# Control_Unit.net
KiCad netlist of a schematic drawn in EAGLE
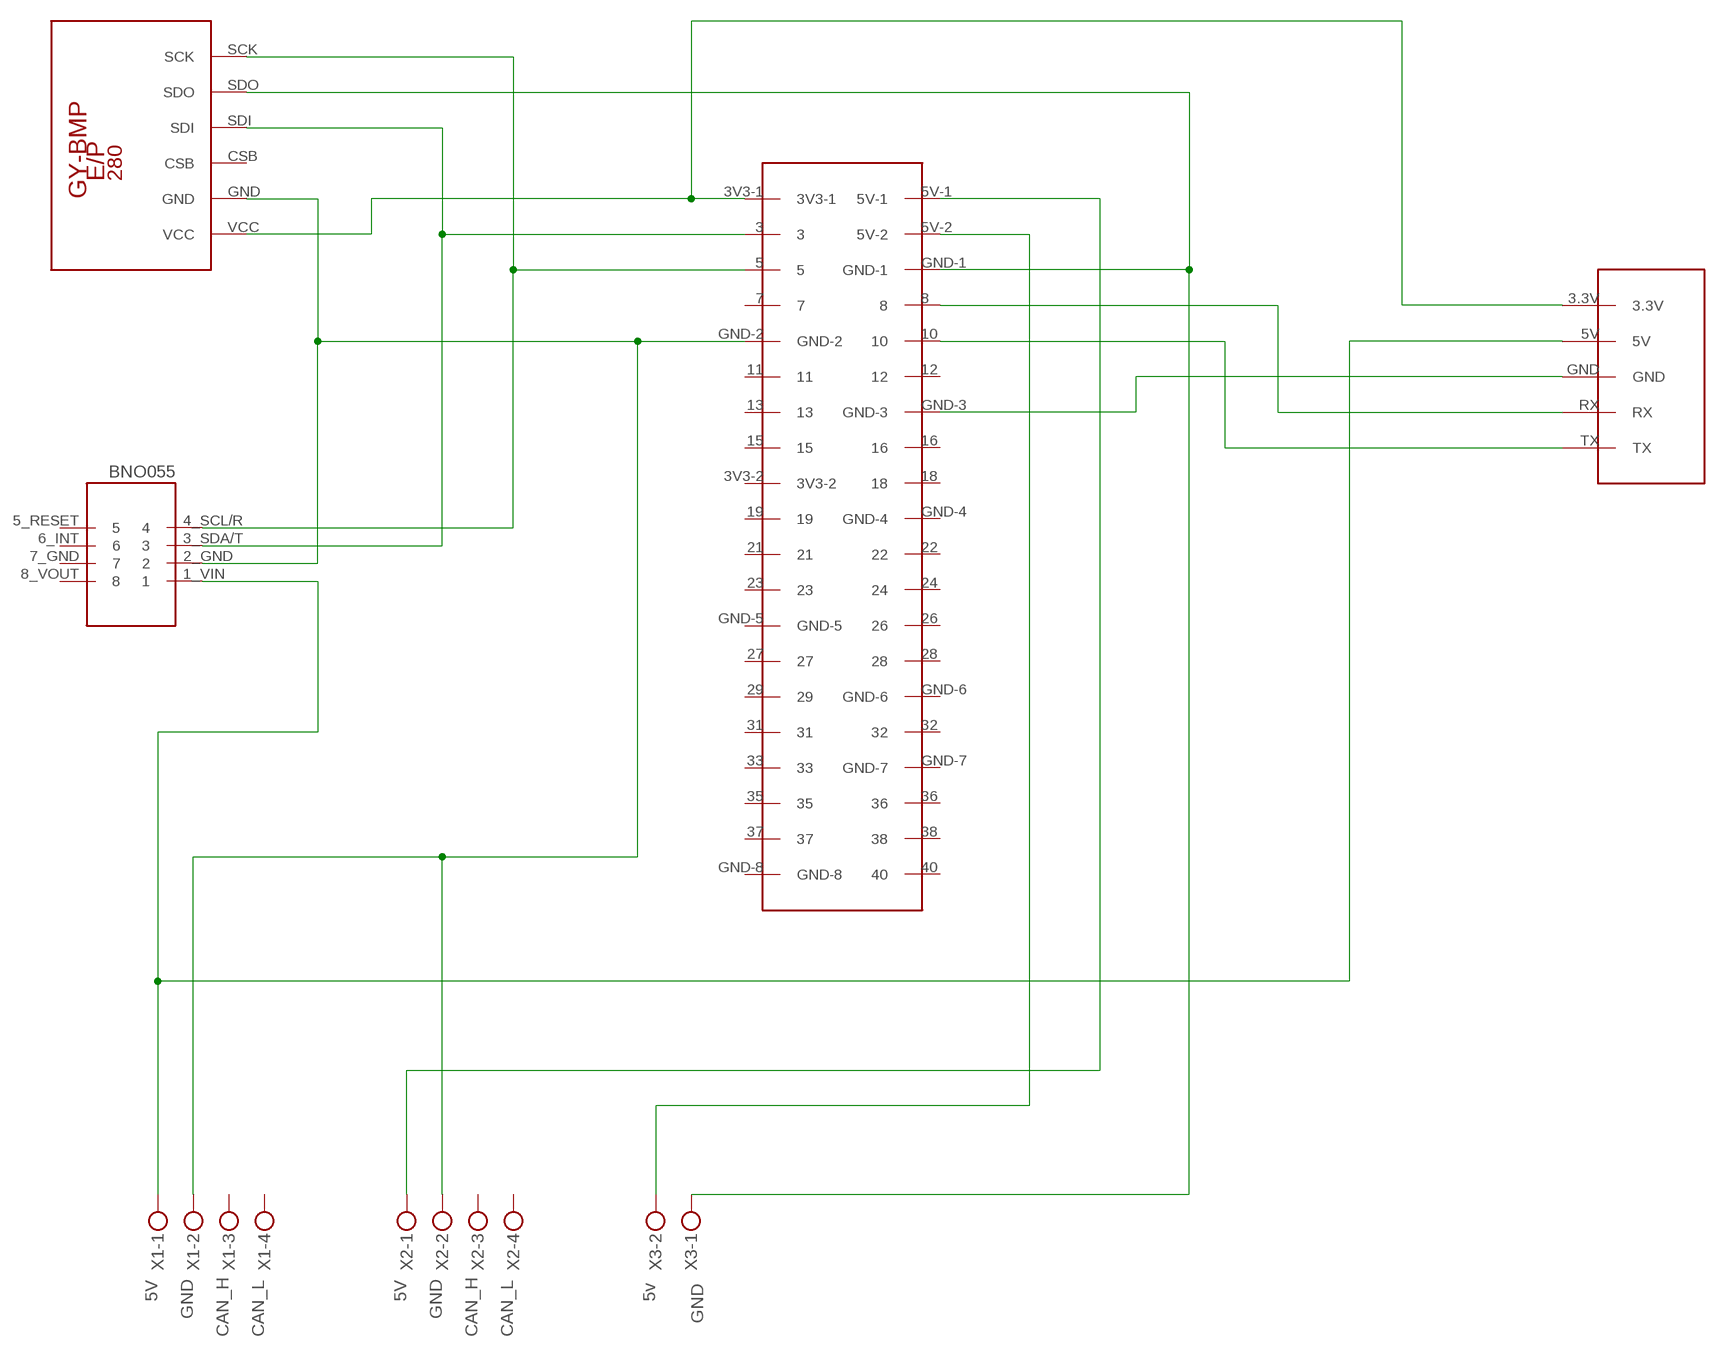
[diagram p0: schematic, sheet 1]

(export (version "E")
  (design (tool "Eeschema 10.0.6"))
  (components
    (comp (ref "JN1")
      (value "JETSON_NANO")
      (footprint "eagle-import:JETSON_NANO")
      (libsource (lib "eagle-import") (part "JETSON_NANO"))
    )
    (comp (ref "U$1")
      (value "GY-BPM280")
      (footprint "eagle-import:GY-BMP280-FOOTPRINT")
      (libsource (lib "eagle-import") (part "GY-BPM280"))
    )
    (comp (ref "U$2")
      (value "BNO055")
      (footprint "eagle-import:BNO055")
      (libsource (lib "eagle-import") (part "BNO055"))
    )
    (comp (ref "U$3")
      (value "WIRELESS_PINS")
      (footprint "eagle-import:WIRELESS_PINS")
      (libsource (lib "eagle-import") (part "WIRELESS_PINS"))
    )
    (comp (ref "X1")
      (value "MKDSN1,5/4-5,08")
      (footprint "eagle-import:MKDSN1,5_4-5,08")
      (libsource (lib "eagle-import") (part "MKDSN1,5/4-5,08"))
    )
    (comp (ref "X2")
      (value "MKDSN1,5/4-5,08")
      (footprint "eagle-import:MKDSN1,5_4-5,08")
      (libsource (lib "eagle-import") (part "MKDSN1,5/4-5,08"))
    )
    (comp (ref "X3")
      (value "MKDSN1,5/2-5,08")
      (footprint "eagle-import:MKDSN1,5_2-5,08")
      (libsource (lib "eagle-import") (part "MKDSN1,5/2-5,08"))
    )
  )
  (nets
    (net (code "1") (name "Net-(JN1-Pad3V3-1)") (class "Default")
      (node (ref "JN1") (pin "3V3-1") (pinfunction "3V3-1_3V3-1") (pintype "bidirectional"))
      (node (ref "U$1") (pin "VCC") (pinfunction "VCC_VCC") (pintype "bidirectional"))
      (node (ref "U$3") (pin "3.3V") (pinfunction "3.3V_3.3V") (pintype "bidirectional"))
    )
    (net (code "2") (name "Net-(JN1-Pad8)") (class "Default")
      (node (ref "JN1") (pin "8") (pinfunction "8_8") (pintype "bidirectional"))
      (node (ref "U$3") (pin "RX") (pinfunction "RX_RX") (pintype "bidirectional"))
    )
    (net (code "3") (name "Net-(JN1-Pad10)") (class "Default")
      (node (ref "JN1") (pin "10") (pinfunction "10_10") (pintype "bidirectional"))
      (node (ref "U$3") (pin "TX") (pinfunction "TX_TX") (pintype "bidirectional"))
    )
    (net (code "4") (name "Net-(JN1-PadGND-3)") (class "Default")
      (node (ref "JN1") (pin "GND-3") (pinfunction "GND-3_GND-3") (pintype "bidirectional"))
      (node (ref "U$3") (pin "GND") (pinfunction "GND_GND") (pintype "bidirectional"))
    )
    (net (code "5") (name "Net-(U$2-1)") (class "Default")
      (node (ref "U$2") (pin "1_VIN") (pinfunction "1_1_VIN") (pintype "bidirectional"))
      (node (ref "U$3") (pin "5V") (pinfunction "5V_5V") (pintype "bidirectional"))
      (node (ref "X1") (pin "1") (pinfunction "KL_1") (pintype "passive"))
    )
    (net (code "6") (name "Net-(U$2-2)") (class "Default")
      (node (ref "JN1") (pin "GND-2") (pinfunction "GND-2_GND-2") (pintype "bidirectional"))
      (node (ref "U$1") (pin "GND") (pinfunction "GND_GND") (pintype "bidirectional"))
      (node (ref "U$2") (pin "2_GND") (pinfunction "2_2_GND") (pintype "bidirectional"))
      (node (ref "X1") (pin "2") (pinfunction "KL_2") (pintype "passive"))
      (node (ref "X2") (pin "2") (pinfunction "KL_2") (pintype "passive"))
    )
    (net (code "7") (name "Net-(U$2-3)") (class "Default")
      (node (ref "JN1") (pin "3") (pinfunction "3_3") (pintype "bidirectional"))
      (node (ref "U$1") (pin "SDI") (pinfunction "SDI_SDI") (pintype "bidirectional"))
      (node (ref "U$2") (pin "3_SDA/T") (pinfunction "3_3_SDA/T") (pintype "bidirectional"))
    )
    (net (code "8") (name "Net-(U$2-4)") (class "Default")
      (node (ref "JN1") (pin "5") (pinfunction "5_5") (pintype "bidirectional"))
      (node (ref "U$1") (pin "SCK") (pinfunction "SCK_SCK") (pintype "bidirectional"))
      (node (ref "U$2") (pin "4_SCL/R") (pinfunction "4_4_SCL/R") (pintype "bidirectional"))
    )
    (net (code "9") (name "Net-(X2A-KL)") (class "Default")
      (node (ref "JN1") (pin "5V-1") (pinfunction "5V-1_5V-1") (pintype "bidirectional"))
      (node (ref "X2") (pin "1") (pinfunction "KL_1") (pintype "passive"))
    )
    (net (code "10") (name "Net-(X3A-KL)") (class "Default")
      (node (ref "JN1") (pin "GND-1") (pinfunction "GND-1_GND-1") (pintype "bidirectional"))
      (node (ref "U$1") (pin "SDO") (pinfunction "SDO_SDO") (pintype "bidirectional"))
      (node (ref "X3") (pin "1") (pinfunction "KL_1") (pintype "passive"))
    )
    (net (code "11") (name "Net-(X3B-KL)") (class "Default")
      (node (ref "JN1") (pin "5V-2") (pinfunction "5V-2_5V-2") (pintype "bidirectional"))
      (node (ref "X3") (pin "2") (pinfunction "KL_2") (pintype "passive"))
    )
    (net (code "12") (name "unconnected-(JN1-Pad3V3-2)") (class "Default")
      (node (ref "JN1") (pin "3V3-2") (pinfunction "3V3-2_3V3-2") (pintype "bidirectional"))
    )
    (net (code "13") (name "unconnected-(JN1-Pad7)") (class "Default")
      (node (ref "JN1") (pin "7") (pinfunction "7_7") (pintype "bidirectional"))
    )
    (net (code "14") (name "unconnected-(JN1-Pad11)") (class "Default")
      (node (ref "JN1") (pin "11") (pinfunction "11_11") (pintype "bidirectional"))
    )
    (net (code "15") (name "unconnected-(JN1-Pad12)") (class "Default")
      (node (ref "JN1") (pin "12") (pinfunction "12_12") (pintype "bidirectional"))
    )
    (net (code "16") (name "unconnected-(JN1-Pad13)") (class "Default")
      (node (ref "JN1") (pin "13") (pinfunction "13_13") (pintype "bidirectional"))
    )
    (net (code "17") (name "unconnected-(JN1-Pad15)") (class "Default")
      (node (ref "JN1") (pin "15") (pinfunction "15_15") (pintype "bidirectional"))
    )
    (net (code "18") (name "unconnected-(JN1-Pad16)") (class "Default")
      (node (ref "JN1") (pin "16") (pinfunction "16_16") (pintype "bidirectional"))
    )
    (net (code "19") (name "unconnected-(JN1-Pad18)") (class "Default")
      (node (ref "JN1") (pin "18") (pinfunction "18_18") (pintype "bidirectional"))
    )
    (net (code "20") (name "unconnected-(JN1-Pad19)") (class "Default")
      (node (ref "JN1") (pin "19") (pinfunction "19_19") (pintype "bidirectional"))
    )
    (net (code "21") (name "unconnected-(JN1-Pad21)") (class "Default")
      (node (ref "JN1") (pin "21") (pinfunction "21_21") (pintype "bidirectional"))
    )
    (net (code "22") (name "unconnected-(JN1-Pad22)") (class "Default")
      (node (ref "JN1") (pin "22") (pinfunction "22_22") (pintype "bidirectional"))
    )
    (net (code "23") (name "unconnected-(JN1-Pad23)") (class "Default")
      (node (ref "JN1") (pin "23") (pinfunction "23_23") (pintype "bidirectional"))
    )
    (net (code "24") (name "unconnected-(JN1-Pad24)") (class "Default")
      (node (ref "JN1") (pin "24") (pinfunction "24_24") (pintype "bidirectional"))
    )
    (net (code "25") (name "unconnected-(JN1-Pad26)") (class "Default")
      (node (ref "JN1") (pin "26") (pinfunction "26_26") (pintype "bidirectional"))
    )
    (net (code "26") (name "unconnected-(JN1-Pad27)") (class "Default")
      (node (ref "JN1") (pin "27") (pinfunction "27_27") (pintype "bidirectional"))
    )
    (net (code "27") (name "unconnected-(JN1-Pad28)") (class "Default")
      (node (ref "JN1") (pin "28") (pinfunction "28_28") (pintype "bidirectional"))
    )
    (net (code "28") (name "unconnected-(JN1-Pad29)") (class "Default")
      (node (ref "JN1") (pin "29") (pinfunction "29_29") (pintype "bidirectional"))
    )
    (net (code "29") (name "unconnected-(JN1-Pad31)") (class "Default")
      (node (ref "JN1") (pin "31") (pinfunction "31_31") (pintype "bidirectional"))
    )
    (net (code "30") (name "unconnected-(JN1-Pad32)") (class "Default")
      (node (ref "JN1") (pin "32") (pinfunction "32_32") (pintype "bidirectional"))
    )
    (net (code "31") (name "unconnected-(JN1-Pad33)") (class "Default")
      (node (ref "JN1") (pin "33") (pinfunction "33_33") (pintype "bidirectional"))
    )
    (net (code "32") (name "unconnected-(JN1-Pad35)") (class "Default")
      (node (ref "JN1") (pin "35") (pinfunction "35_35") (pintype "bidirectional"))
    )
    (net (code "33") (name "unconnected-(JN1-Pad36)") (class "Default")
      (node (ref "JN1") (pin "36") (pinfunction "36_36") (pintype "bidirectional"))
    )
    (net (code "34") (name "unconnected-(JN1-Pad37)") (class "Default")
      (node (ref "JN1") (pin "37") (pinfunction "37_37") (pintype "bidirectional"))
    )
    (net (code "35") (name "unconnected-(JN1-Pad38)") (class "Default")
      (node (ref "JN1") (pin "38") (pinfunction "38_38") (pintype "bidirectional"))
    )
    (net (code "36") (name "unconnected-(JN1-Pad40)") (class "Default")
      (node (ref "JN1") (pin "40") (pinfunction "40_40") (pintype "bidirectional"))
    )
    (net (code "37") (name "unconnected-(JN1-PadGND-4)") (class "Default")
      (node (ref "JN1") (pin "GND-4") (pinfunction "GND-4_GND-4") (pintype "bidirectional"))
    )
    (net (code "38") (name "unconnected-(JN1-PadGND-5)") (class "Default")
      (node (ref "JN1") (pin "GND-5") (pinfunction "GND-5_GND-5") (pintype "bidirectional"))
    )
    (net (code "39") (name "unconnected-(JN1-PadGND-6)") (class "Default")
      (node (ref "JN1") (pin "GND-6") (pinfunction "GND-6_GND-6") (pintype "bidirectional"))
    )
    (net (code "40") (name "unconnected-(JN1-PadGND-7)") (class "Default")
      (node (ref "JN1") (pin "GND-7") (pinfunction "GND-7_GND-7") (pintype "bidirectional"))
    )
    (net (code "41") (name "unconnected-(JN1-PadGND-8)") (class "Default")
      (node (ref "JN1") (pin "GND-8") (pinfunction "GND-8_GND-8") (pintype "bidirectional"))
    )
    (net (code "42") (name "unconnected-(U$1-PadCSB)") (class "Default")
      (node (ref "U$1") (pin "CSB") (pinfunction "CSB_CSB") (pintype "bidirectional"))
    )
    (net (code "43") (name "unconnected-(U$2-5-Pad5_RESET)") (class "Default")
      (node (ref "U$2") (pin "5_RESET") (pinfunction "5_5_RESET") (pintype "bidirectional"))
    )
    (net (code "44") (name "unconnected-(U$2-6-Pad6_INT)") (class "Default")
      (node (ref "U$2") (pin "6_INT") (pinfunction "6_6_INT") (pintype "bidirectional"))
    )
    (net (code "45") (name "unconnected-(U$2-7-Pad7_GND)") (class "Default")
      (node (ref "U$2") (pin "7_GND") (pinfunction "7_7_GND") (pintype "bidirectional"))
    )
    (net (code "46") (name "unconnected-(U$2-8-Pad8_VOUT)") (class "Default")
      (node (ref "U$2") (pin "8_VOUT") (pinfunction "8_8_VOUT") (pintype "bidirectional"))
    )
    (net (code "47") (name "unconnected-(X1C-KL-Pad3)") (class "Default")
      (node (ref "X1") (pin "3") (pinfunction "KL_3") (pintype "passive"))
    )
    (net (code "48") (name "unconnected-(X1D-KL-Pad4)") (class "Default")
      (node (ref "X1") (pin "4") (pinfunction "KL_4") (pintype "passive"))
    )
    (net (code "49") (name "unconnected-(X2C-KL-Pad3)") (class "Default")
      (node (ref "X2") (pin "3") (pinfunction "KL_3") (pintype "passive"))
    )
    (net (code "50") (name "unconnected-(X2D-KL-Pad4)") (class "Default")
      (node (ref "X2") (pin "4") (pinfunction "KL_4") (pintype "passive"))
    )
  )
)
